# power.net
KiCad netlist of a schematic drawn in Altium Designer
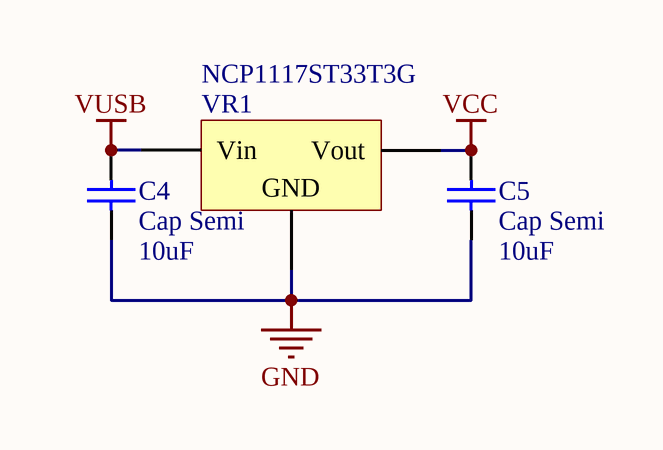
[diagram p0: power.SchDoc]

(export (version "E")
  (design (tool "Eeschema 10.0.6"))
  (components
    (comp (ref "C4")
      (value "Cap Semi")
      (footprint "CAPC1608L")
      (description "Capacitor (Semiconductor SIM Model)")
      (fields (field (name "ALTIUM_VALUE") "10uF") (field (name "PUBLISHER") "Altium Limited"))
      (libsource (lib "Miscellaneous Devices") (part "Cap Semi"))
    )
    (comp (ref "C5")
      (value "Cap Semi")
      (footprint "CAPC1608L")
      (description "Capacitor (Semiconductor SIM Model)")
      (fields (field (name "ALTIUM_VALUE") "10uF") (field (name "PUBLISHER") "Altium Limited"))
      (libsource (lib "Miscellaneous Devices") (part "Cap Semi"))
    )
    (comp (ref "VR1")
      (value "NCP1117ST33T3G")
      (footprint "SOT223-4N")
      (description "Voltage Regulator")
      (fields (field (name "PUBLISHER") "Altium Limited"))
      (libsource (lib "Miscellaneous Devices") (part "Volt Reg"))
    )
  )
  (nets
    (net (code "1") (name "GND") (class "Default")
      (node (ref "C4") (pin "1") (pinfunction "1_1") (pintype "passive"))
      (node (ref "C5") (pin "1") (pinfunction "1_1") (pintype "passive"))
      (node (ref "VR1") (pin "2") (pinfunction "GND_2") (pintype "passive"))
    )
    (net (code "2") (name "VCC") (class "Default")
      (node (ref "C5") (pin "2") (pinfunction "2_2") (pintype "passive"))
      (node (ref "VR1") (pin "3") (pinfunction "Vout_3") (pintype "passive"))
    )
    (net (code "3") (name "VUSB") (class "Default")
      (node (ref "C4") (pin "2") (pinfunction "2_2") (pintype "passive"))
      (node (ref "VR1") (pin "1") (pinfunction "Vin_1") (pintype "passive"))
    )
  )
)
